# v001.net
KiCad netlist of a schematic drawn in EAGLE
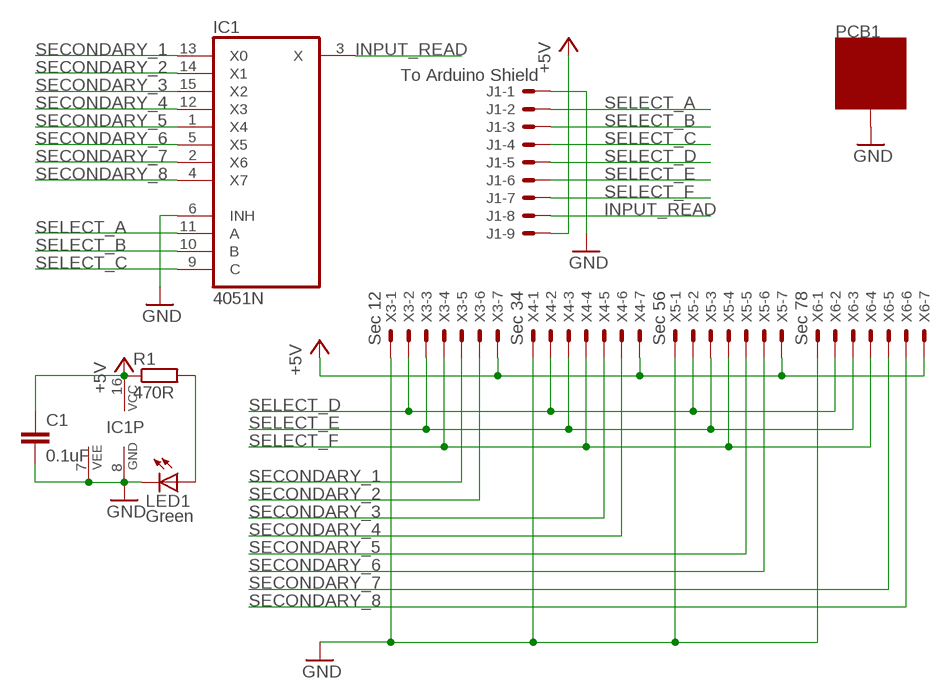
[diagram p0: schematic, sheet 1]

(export (version "E")
  (design (tool "Eeschema 10.0.6"))
  (components
    (comp (ref "C1")
      (value "0.1uF")
      (footprint "eagle-import:C050-024X044")
      (libsource (lib "eagle-import") (part "C-EU050-024X044"))
    )
    (comp (ref "IC1")
      (value "4051N")
      (footprint "eagle-import:DIL16")
      (libsource (lib "eagle-import") (part "4051N"))
    )
    (comp (ref "J1")
      (value "To Arduino Shield")
      (footprint "eagle-import:6410-09")
      (libsource (lib "eagle-import") (part "22-?-0927-2091"))
    )
    (comp (ref "LED1")
      (value "Green")
      (footprint "eagle-import:LED3MM")
      (libsource (lib "eagle-import") (part "LED3MM"))
    )
    (comp (ref "PCB1")
      (value "ZZZ_MODULE05X05")
      (footprint "eagle-import:ZZZ_MODULE_05X05")
      (libsource (lib "eagle-import") (part "ZZZ_MODULE05X05"))
    )
    (comp (ref "R1")
      (value "470R")
      (footprint "eagle-import:0204_7")
      (libsource (lib "eagle-import") (part "R-EU_0204/7"))
    )
    (comp (ref "X3")
      (value "Sec 12")
      (footprint "eagle-import:6410-07")
      (libsource (lib "eagle-import") (part "22-?-0727-2071"))
    )
    (comp (ref "X4")
      (value "Sec 34")
      (footprint "eagle-import:6410-07")
      (libsource (lib "eagle-import") (part "22-?-0727-2071"))
    )
    (comp (ref "X5")
      (value "Sec 56")
      (footprint "eagle-import:6410-07")
      (libsource (lib "eagle-import") (part "22-?-0727-2071"))
    )
    (comp (ref "X6")
      (value "Sec 78")
      (footprint "eagle-import:6410-07")
      (libsource (lib "eagle-import") (part "22-?-0727-2071"))
    )
  )
  (nets
    (net (code "1") (name "+5V") (class "Default")
      (node (ref "C1") (pin "1") (pinfunction "1_1") (pintype "passive"))
      (node (ref "IC1") (pin "16") (pinfunction "VCC_16") (pintype "power_in"))
      (node (ref "J1") (pin "9") (pinfunction "S_9") (pintype "passive"))
      (node (ref "R1") (pin "1") (pinfunction "1_1") (pintype "passive"))
      (node (ref "X3") (pin "7") (pinfunction "S_7") (pintype "passive"))
      (node (ref "X4") (pin "7") (pinfunction "S_7") (pintype "passive"))
      (node (ref "X5") (pin "7") (pinfunction "S_7") (pintype "passive"))
      (node (ref "X6") (pin "7") (pinfunction "S_7") (pintype "passive"))
    )
    (net (code "2") (name "/INPUT_READ") (class "Default")
      (node (ref "IC1") (pin "3") (pinfunction "X_3") (pintype "bidirectional"))
      (node (ref "J1") (pin "8") (pinfunction "S_8") (pintype "passive"))
    )
    (net (code "3") (name "/SECONDARY_1") (class "Default")
      (node (ref "IC1") (pin "13") (pinfunction "X0_13") (pintype "bidirectional"))
      (node (ref "X3") (pin "5") (pinfunction "S_5") (pintype "passive"))
    )
    (net (code "4") (name "/SECONDARY_2") (class "Default")
      (node (ref "IC1") (pin "14") (pinfunction "X1_14") (pintype "bidirectional"))
      (node (ref "X3") (pin "6") (pinfunction "S_6") (pintype "passive"))
    )
    (net (code "5") (name "/SECONDARY_3") (class "Default")
      (node (ref "IC1") (pin "15") (pinfunction "X2_15") (pintype "bidirectional"))
      (node (ref "X4") (pin "5") (pinfunction "S_5") (pintype "passive"))
    )
    (net (code "6") (name "/SECONDARY_4") (class "Default")
      (node (ref "IC1") (pin "12") (pinfunction "X3_12") (pintype "bidirectional"))
      (node (ref "X4") (pin "6") (pinfunction "S_6") (pintype "passive"))
    )
    (net (code "7") (name "/SECONDARY_5") (class "Default")
      (node (ref "IC1") (pin "1") (pinfunction "X4_1") (pintype "bidirectional"))
      (node (ref "X5") (pin "5") (pinfunction "S_5") (pintype "passive"))
    )
    (net (code "8") (name "/SECONDARY_6") (class "Default")
      (node (ref "IC1") (pin "5") (pinfunction "X5_5") (pintype "bidirectional"))
      (node (ref "X5") (pin "6") (pinfunction "S_6") (pintype "passive"))
    )
    (net (code "9") (name "/SECONDARY_7") (class "Default")
      (node (ref "IC1") (pin "2") (pinfunction "X6_2") (pintype "bidirectional"))
      (node (ref "X6") (pin "5") (pinfunction "S_5") (pintype "passive"))
    )
    (net (code "10") (name "/SECONDARY_8") (class "Default")
      (node (ref "IC1") (pin "4") (pinfunction "X7_4") (pintype "bidirectional"))
      (node (ref "X6") (pin "6") (pinfunction "S_6") (pintype "passive"))
    )
    (net (code "11") (name "/SELECT_A") (class "Default")
      (node (ref "IC1") (pin "11") (pinfunction "A_11") (pintype "input"))
      (node (ref "J1") (pin "2") (pinfunction "S_2") (pintype "passive"))
    )
    (net (code "12") (name "/SELECT_B") (class "Default")
      (node (ref "IC1") (pin "10") (pinfunction "B_10") (pintype "input"))
      (node (ref "J1") (pin "3") (pinfunction "S_3") (pintype "passive"))
    )
    (net (code "13") (name "/SELECT_C") (class "Default")
      (node (ref "IC1") (pin "9") (pinfunction "C_9") (pintype "input"))
      (node (ref "J1") (pin "4") (pinfunction "S_4") (pintype "passive"))
    )
    (net (code "14") (name "/SELECT_D") (class "Default")
      (node (ref "J1") (pin "5") (pinfunction "S_5") (pintype "passive"))
      (node (ref "X3") (pin "2") (pinfunction "S_2") (pintype "passive"))
      (node (ref "X4") (pin "2") (pinfunction "S_2") (pintype "passive"))
      (node (ref "X5") (pin "2") (pinfunction "S_2") (pintype "passive"))
      (node (ref "X6") (pin "2") (pinfunction "S_2") (pintype "passive"))
    )
    (net (code "15") (name "/SELECT_E") (class "Default")
      (node (ref "J1") (pin "6") (pinfunction "S_6") (pintype "passive"))
      (node (ref "X3") (pin "3") (pinfunction "S_3") (pintype "passive"))
      (node (ref "X4") (pin "3") (pinfunction "S_3") (pintype "passive"))
      (node (ref "X5") (pin "3") (pinfunction "S_3") (pintype "passive"))
      (node (ref "X6") (pin "3") (pinfunction "S_3") (pintype "passive"))
    )
    (net (code "16") (name "/SELECT_F") (class "Default")
      (node (ref "J1") (pin "7") (pinfunction "S_7") (pintype "passive"))
      (node (ref "X3") (pin "4") (pinfunction "S_4") (pintype "passive"))
      (node (ref "X4") (pin "4") (pinfunction "S_4") (pintype "passive"))
      (node (ref "X5") (pin "4") (pinfunction "S_4") (pintype "passive"))
      (node (ref "X6") (pin "4") (pinfunction "S_4") (pintype "passive"))
    )
    (net (code "17") (name "GND") (class "Default")
      (node (ref "C1") (pin "2") (pinfunction "2_2") (pintype "passive"))
      (node (ref "IC1") (pin "6") (pinfunction "INH_6") (pintype "input"))
      (node (ref "IC1") (pin "7") (pinfunction "VEE_7") (pintype "power_in"))
      (node (ref "IC1") (pin "8") (pinfunction "GND_8") (pintype "power_in"))
      (node (ref "J1") (pin "1") (pinfunction "S_1") (pintype "passive"))
      (node (ref "LED1") (pin "K") (pinfunction "C_K") (pintype "passive"))
      (node (ref "PCB1") (pin "GND@1") (pinfunction "GND_GND@1") (pintype "power_in"))
      (node (ref "PCB1") (pin "GND@2") (pinfunction "GND_GND@2") (pintype "power_in"))
      (node (ref "PCB1") (pin "GND@3") (pinfunction "GND_GND@3") (pintype "power_in"))
      (node (ref "PCB1") (pin "GND@4") (pinfunction "GND_GND@4") (pintype "power_in"))
      (node (ref "PCB1") (pin "GND@5") (pinfunction "GND_GND@5") (pintype "power_in"))
      (node (ref "PCB1") (pin "GND@6") (pinfunction "GND_GND@6") (pintype "power_in"))
      (node (ref "PCB1") (pin "GND@7") (pinfunction "GND_GND@7") (pintype "power_in"))
      (node (ref "PCB1") (pin "GND@8") (pinfunction "GND_GND@8") (pintype "power_in"))
      (node (ref "X3") (pin "1") (pinfunction "S_1") (pintype "passive"))
      (node (ref "X4") (pin "1") (pinfunction "S_1") (pintype "passive"))
      (node (ref "X5") (pin "1") (pinfunction "S_1") (pintype "passive"))
      (node (ref "X6") (pin "1") (pinfunction "S_1") (pintype "passive"))
    )
    (net (code "18") (name "Net-(LED1-PadA)") (class "Default")
      (node (ref "LED1") (pin "A") (pinfunction "A_A") (pintype "passive"))
      (node (ref "R1") (pin "2") (pinfunction "2_2") (pintype "passive"))
    )
  )
)
